# optoisolator-shield.net
KiCad netlist of a schematic drawn in EAGLE
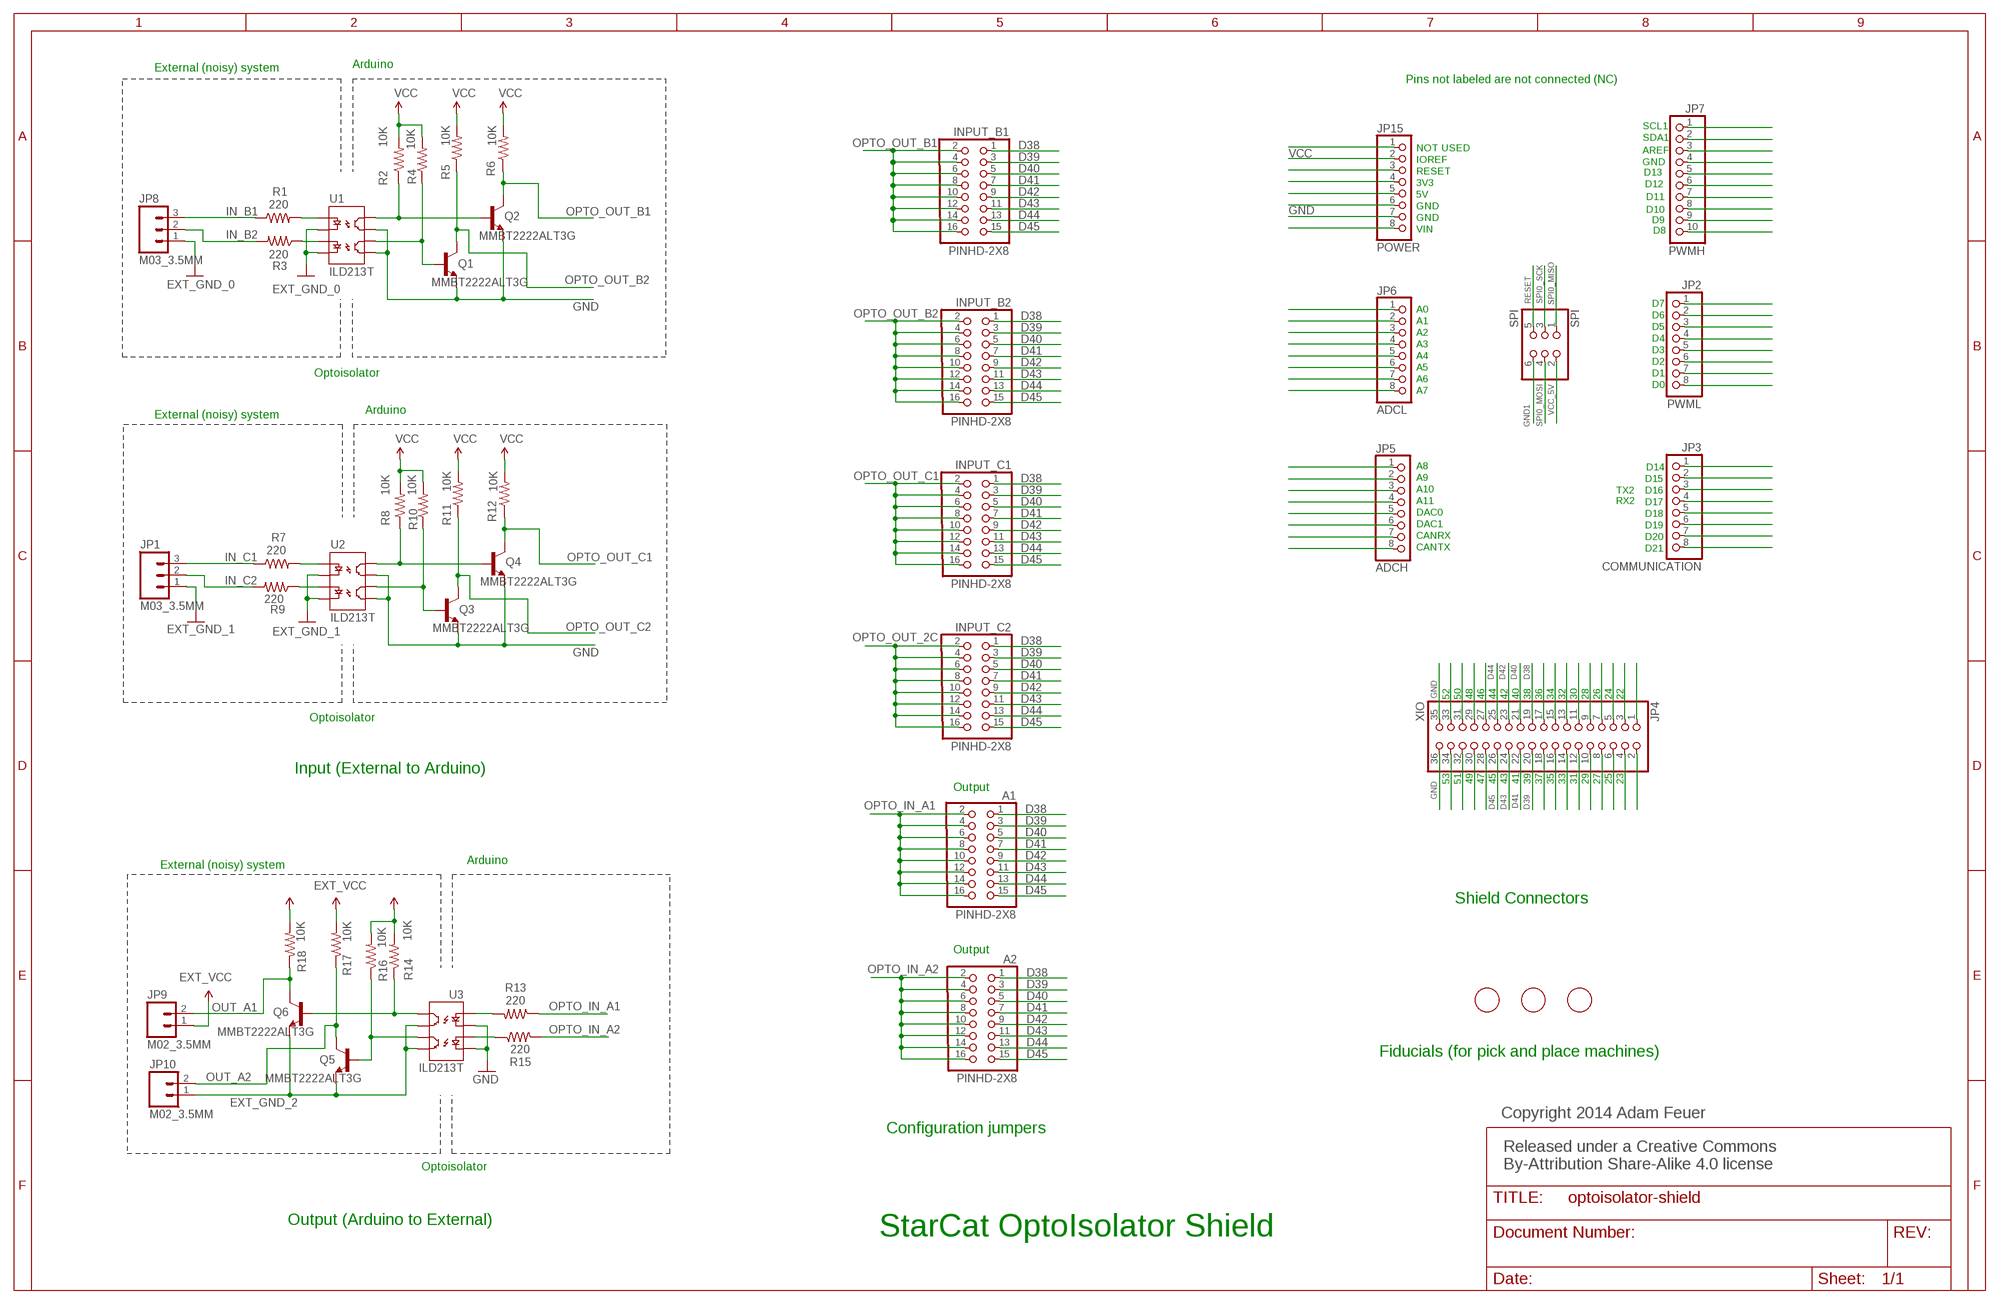
[diagram p0: schematic, sheet 1]

(export (version "E")
  (design (tool "Eeschema 10.0.6"))
  (components
    (comp (ref "A1")
      (value "PINHD-2X8")
      (footprint "eagle-import:2X08")
      (libsource (lib "eagle-import") (part "PINHD-2X8"))
    )
    (comp (ref "A2")
      (value "PINHD-2X8")
      (footprint "eagle-import:2X08")
      (libsource (lib "eagle-import") (part "PINHD-2X8"))
    )
    (comp (ref "INPUT_B1")
      (value "PINHD-2X8")
      (footprint "eagle-import:2X08")
      (libsource (lib "eagle-import") (part "PINHD-2X8"))
    )
    (comp (ref "INPUT_B2")
      (value "PINHD-2X8")
      (footprint "eagle-import:2X08")
      (libsource (lib "eagle-import") (part "PINHD-2X8"))
    )
    (comp (ref "INPUT_C1")
      (value "PINHD-2X8")
      (footprint "eagle-import:2X08")
      (libsource (lib "eagle-import") (part "PINHD-2X8"))
    )
    (comp (ref "INPUT_C2")
      (value "PINHD-2X8")
      (footprint "eagle-import:2X08")
      (libsource (lib "eagle-import") (part "PINHD-2X8"))
    )
    (comp (ref "JP1")
      (value "M03_3.5MM")
      (footprint "eagle-import:SCREWTERMINAL-3.5MM-3")
      (libsource (lib "eagle-import") (part "M03SCREW"))
    )
    (comp (ref "JP2")
      (value "PWML")
      (footprint "eagle-import:1X08")
      (libsource (lib "eagle-import") (part "PINHD-1X8"))
    )
    (comp (ref "JP3")
      (value "COMMUNICATION")
      (footprint "eagle-import:1X08")
      (libsource (lib "eagle-import") (part "PINHD-1X8"))
    )
    (comp (ref "JP4")
      (value "XIO")
      (footprint "eagle-import:2X18")
      (libsource (lib "eagle-import") (part "PINHD-2X18"))
    )
    (comp (ref "JP5")
      (value "ADCH")
      (footprint "eagle-import:1X08")
      (libsource (lib "eagle-import") (part "PINHD-1X8"))
    )
    (comp (ref "JP6")
      (value "ADCL")
      (footprint "eagle-import:1X08")
      (libsource (lib "eagle-import") (part "PINHD-1X8"))
    )
    (comp (ref "JP7")
      (value "PWMH")
      (footprint "eagle-import:1X10")
      (libsource (lib "eagle-import") (part "PINHD-1X10"))
    )
    (comp (ref "JP8")
      (value "M03_3.5MM")
      (footprint "eagle-import:SCREWTERMINAL-3.5MM-3")
      (libsource (lib "eagle-import") (part "M03SCREW"))
    )
    (comp (ref "JP9")
      (value "M02_3.5MM")
      (footprint "eagle-import:SCREWTERMINAL-3.5MM-2")
      (libsource (lib "eagle-import") (part "M023.5MM"))
    )
    (comp (ref "JP10")
      (value "M02_3.5MM")
      (footprint "eagle-import:SCREWTERMINAL-3.5MM-2")
      (libsource (lib "eagle-import") (part "M023.5MM"))
    )
    (comp (ref "JP15")
      (value "POWER")
      (footprint "eagle-import:1X08")
      (libsource (lib "eagle-import") (part "PINHD-1X8"))
    )
    (comp (ref "Q1")
      (value "MMBT2222ALT3G")
      (footprint "eagle-import:SOT23-3")
      (libsource (lib "eagle-import") (part "TRANSISTOR_NPNSOT23-3"))
    )
    (comp (ref "Q2")
      (value "MMBT2222ALT3G")
      (footprint "eagle-import:SOT23-3")
      (libsource (lib "eagle-import") (part "TRANSISTOR_NPNSOT23-3"))
    )
    (comp (ref "Q3")
      (value "MMBT2222ALT3G")
      (footprint "eagle-import:SOT23-3")
      (libsource (lib "eagle-import") (part "TRANSISTOR_NPNSOT23-3"))
    )
    (comp (ref "Q4")
      (value "MMBT2222ALT3G")
      (footprint "eagle-import:SOT23-3")
      (libsource (lib "eagle-import") (part "TRANSISTOR_NPNSOT23-3"))
    )
    (comp (ref "Q5")
      (value "MMBT2222ALT3G")
      (footprint "eagle-import:SOT23-3")
      (libsource (lib "eagle-import") (part "TRANSISTOR_NPNSOT23-3"))
    )
    (comp (ref "Q6")
      (value "MMBT2222ALT3G")
      (footprint "eagle-import:SOT23-3")
      (libsource (lib "eagle-import") (part "TRANSISTOR_NPNSOT23-3"))
    )
    (comp (ref "R1")
      (value "220")
      (footprint "eagle-import:0603-RES")
      (libsource (lib "eagle-import") (part "RESISTOR0603-RES"))
    )
    (comp (ref "R2")
      (value "10K")
      (footprint "eagle-import:0603-RES")
      (libsource (lib "eagle-import") (part "RESISTOR0603-RES"))
    )
    (comp (ref "R3")
      (value "220")
      (footprint "eagle-import:0603-RES")
      (libsource (lib "eagle-import") (part "RESISTOR0603-RES"))
    )
    (comp (ref "R4")
      (value "10K")
      (footprint "eagle-import:0603-RES")
      (libsource (lib "eagle-import") (part "RESISTOR0603-RES"))
    )
    (comp (ref "R5")
      (value "10K")
      (footprint "eagle-import:0603-RES")
      (libsource (lib "eagle-import") (part "RESISTOR0603-RES"))
    )
    (comp (ref "R6")
      (value "10K")
      (footprint "eagle-import:0603-RES")
      (libsource (lib "eagle-import") (part "RESISTOR0603-RES"))
    )
    (comp (ref "R7")
      (value "220")
      (footprint "eagle-import:0603-RES")
      (libsource (lib "eagle-import") (part "RESISTOR0603-RES"))
    )
    (comp (ref "R8")
      (value "10K")
      (footprint "eagle-import:0603-RES")
      (libsource (lib "eagle-import") (part "RESISTOR0603-RES"))
    )
    (comp (ref "R9")
      (value "220")
      (footprint "eagle-import:0603-RES")
      (libsource (lib "eagle-import") (part "RESISTOR0603-RES"))
    )
    (comp (ref "R10")
      (value "10K")
      (footprint "eagle-import:0603-RES")
      (libsource (lib "eagle-import") (part "RESISTOR0603-RES"))
    )
    (comp (ref "R11")
      (value "10K")
      (footprint "eagle-import:0603-RES")
      (libsource (lib "eagle-import") (part "RESISTOR0603-RES"))
    )
    (comp (ref "R12")
      (value "10K")
      (footprint "eagle-import:0603-RES")
      (libsource (lib "eagle-import") (part "RESISTOR0603-RES"))
    )
    (comp (ref "R13")
      (value "220")
      (footprint "eagle-import:0603-RES")
      (libsource (lib "eagle-import") (part "RESISTOR0603-RES"))
    )
    (comp (ref "R14")
      (value "10K")
      (footprint "eagle-import:0603-RES")
      (libsource (lib "eagle-import") (part "RESISTOR0603-RES"))
    )
    (comp (ref "R15")
      (value "220")
      (footprint "eagle-import:0603-RES")
      (libsource (lib "eagle-import") (part "RESISTOR0603-RES"))
    )
    (comp (ref "R16")
      (value "10K")
      (footprint "eagle-import:0603-RES")
      (libsource (lib "eagle-import") (part "RESISTOR0603-RES"))
    )
    (comp (ref "R17")
      (value "10K")
      (footprint "eagle-import:0603-RES")
      (libsource (lib "eagle-import") (part "RESISTOR0603-RES"))
    )
    (comp (ref "R18")
      (value "10K")
      (footprint "eagle-import:0603-RES")
      (libsource (lib "eagle-import") (part "RESISTOR0603-RES"))
    )
    (comp (ref "SPI")
      (value "SPI")
      (footprint "eagle-import:2X03")
      (libsource (lib "eagle-import") (part "PINHD-2X3"))
    )
    (comp (ref "U$2")
      (value "FIDUCIAL")
      (footprint "eagle-import:FIDUCIAL_1MM")
      (libsource (lib "eagle-import") (part "FIDUCIAL"))
    )
    (comp (ref "U$5")
      (value "FIDUCIAL")
      (footprint "eagle-import:FIDUCIAL_1MM")
      (libsource (lib "eagle-import") (part "FIDUCIAL"))
    )
    (comp (ref "U$6")
      (value "FIDUCIAL")
      (footprint "eagle-import:FIDUCIAL_1MM")
      (libsource (lib "eagle-import") (part "FIDUCIAL"))
    )
    (comp (ref "U1")
      (value "ILD213T")
      (footprint "eagle-import:SO08-2")
      (libsource (lib "eagle-import") (part "OPTOISOLATOR-2SOIC8"))
    )
    (comp (ref "U2")
      (value "ILD213T")
      (footprint "eagle-import:SO08-2")
      (libsource (lib "eagle-import") (part "OPTOISOLATOR-2SOIC8"))
    )
    (comp (ref "U3")
      (value "ILD213T")
      (footprint "eagle-import:SO08-2")
      (libsource (lib "eagle-import") (part "OPTOISOLATOR-2SOIC8"))
    )
  )
  (nets
    (net (code "1") (name "/D38") (class "Default")
      (node (ref "A1") (pin "1") (pinfunction "1_1") (pintype "passive"))
      (node (ref "A2") (pin "1") (pinfunction "1_1") (pintype "passive"))
      (node (ref "INPUT_B1") (pin "1") (pinfunction "1_1") (pintype "passive"))
      (node (ref "INPUT_B2") (pin "1") (pinfunction "1_1") (pintype "passive"))
      (node (ref "INPUT_C1") (pin "1") (pinfunction "1_1") (pintype "passive"))
      (node (ref "INPUT_C2") (pin "1") (pinfunction "1_1") (pintype "passive"))
      (node (ref "JP4") (pin "19") (pinfunction "19_19") (pintype "passive"))
    )
    (net (code "2") (name "/D39") (class "Default")
      (node (ref "A1") (pin "3") (pinfunction "3_3") (pintype "passive"))
      (node (ref "A2") (pin "3") (pinfunction "3_3") (pintype "passive"))
      (node (ref "INPUT_B1") (pin "3") (pinfunction "3_3") (pintype "passive"))
      (node (ref "INPUT_B2") (pin "3") (pinfunction "3_3") (pintype "passive"))
      (node (ref "INPUT_C1") (pin "3") (pinfunction "3_3") (pintype "passive"))
      (node (ref "INPUT_C2") (pin "3") (pinfunction "3_3") (pintype "passive"))
      (node (ref "JP4") (pin "20") (pinfunction "20_20") (pintype "passive"))
    )
    (net (code "3") (name "/D40") (class "Default")
      (node (ref "A1") (pin "5") (pinfunction "5_5") (pintype "passive"))
      (node (ref "A2") (pin "5") (pinfunction "5_5") (pintype "passive"))
      (node (ref "INPUT_B1") (pin "5") (pinfunction "5_5") (pintype "passive"))
      (node (ref "INPUT_B2") (pin "5") (pinfunction "5_5") (pintype "passive"))
      (node (ref "INPUT_C1") (pin "5") (pinfunction "5_5") (pintype "passive"))
      (node (ref "INPUT_C2") (pin "5") (pinfunction "5_5") (pintype "passive"))
      (node (ref "JP4") (pin "21") (pinfunction "21_21") (pintype "passive"))
    )
    (net (code "4") (name "/D41") (class "Default")
      (node (ref "A1") (pin "7") (pinfunction "7_7") (pintype "passive"))
      (node (ref "A2") (pin "7") (pinfunction "7_7") (pintype "passive"))
      (node (ref "INPUT_B1") (pin "7") (pinfunction "7_7") (pintype "passive"))
      (node (ref "INPUT_B2") (pin "7") (pinfunction "7_7") (pintype "passive"))
      (node (ref "INPUT_C1") (pin "7") (pinfunction "7_7") (pintype "passive"))
      (node (ref "INPUT_C2") (pin "7") (pinfunction "7_7") (pintype "passive"))
      (node (ref "JP4") (pin "22") (pinfunction "22_22") (pintype "passive"))
    )
    (net (code "5") (name "/D42") (class "Default")
      (node (ref "A1") (pin "9") (pinfunction "9_9") (pintype "passive"))
      (node (ref "A2") (pin "9") (pinfunction "9_9") (pintype "passive"))
      (node (ref "INPUT_B1") (pin "9") (pinfunction "9_9") (pintype "passive"))
      (node (ref "INPUT_B2") (pin "9") (pinfunction "9_9") (pintype "passive"))
      (node (ref "INPUT_C1") (pin "9") (pinfunction "9_9") (pintype "passive"))
      (node (ref "INPUT_C2") (pin "9") (pinfunction "9_9") (pintype "passive"))
      (node (ref "JP4") (pin "23") (pinfunction "23_23") (pintype "passive"))
    )
    (net (code "6") (name "/D43") (class "Default")
      (node (ref "A1") (pin "11") (pinfunction "11_11") (pintype "passive"))
      (node (ref "A2") (pin "11") (pinfunction "11_11") (pintype "passive"))
      (node (ref "INPUT_B1") (pin "11") (pinfunction "11_11") (pintype "passive"))
      (node (ref "INPUT_B2") (pin "11") (pinfunction "11_11") (pintype "passive"))
      (node (ref "INPUT_C1") (pin "11") (pinfunction "11_11") (pintype "passive"))
      (node (ref "INPUT_C2") (pin "11") (pinfunction "11_11") (pintype "passive"))
      (node (ref "JP4") (pin "24") (pinfunction "24_24") (pintype "passive"))
    )
    (net (code "7") (name "/D44") (class "Default")
      (node (ref "A1") (pin "13") (pinfunction "13_13") (pintype "passive"))
      (node (ref "A2") (pin "13") (pinfunction "13_13") (pintype "passive"))
      (node (ref "INPUT_B1") (pin "13") (pinfunction "13_13") (pintype "passive"))
      (node (ref "INPUT_B2") (pin "13") (pinfunction "13_13") (pintype "passive"))
      (node (ref "INPUT_C1") (pin "13") (pinfunction "13_13") (pintype "passive"))
      (node (ref "INPUT_C2") (pin "13") (pinfunction "13_13") (pintype "passive"))
      (node (ref "JP4") (pin "25") (pinfunction "25_25") (pintype "passive"))
    )
    (net (code "8") (name "/D45") (class "Default")
      (node (ref "A1") (pin "15") (pinfunction "15_15") (pintype "passive"))
      (node (ref "A2") (pin "15") (pinfunction "15_15") (pintype "passive"))
      (node (ref "INPUT_B1") (pin "15") (pinfunction "15_15") (pintype "passive"))
      (node (ref "INPUT_B2") (pin "15") (pinfunction "15_15") (pintype "passive"))
      (node (ref "INPUT_C1") (pin "15") (pinfunction "15_15") (pintype "passive"))
      (node (ref "INPUT_C2") (pin "15") (pinfunction "15_15") (pintype "passive"))
      (node (ref "JP4") (pin "26") (pinfunction "26_26") (pintype "passive"))
    )
    (net (code "9") (name "/EXT_GND_2") (class "Default")
      (node (ref "JP10") (pin "1") (pinfunction "1_1") (pintype "passive"))
      (node (ref "Q5") (pin "2") (pinfunction "E_2") (pintype "passive"))
      (node (ref "Q6") (pin "2") (pinfunction "E_2") (pintype "passive"))
      (node (ref "U3") (pin "5") (pinfunction "EM2_5") (pintype "bidirectional"))
      (node (ref "U3") (pin "7") (pinfunction "EM1_7") (pintype "bidirectional"))
    )
    (net (code "10") (name "/GND1") (class "Default")
      (node (ref "SPI") (pin "6") (pinfunction "6_6") (pintype "passive"))
    )
    (net (code "11") (name "/IN_B1") (class "Default")
      (node (ref "JP8") (pin "3") (pinfunction "3_3") (pintype "passive"))
      (node (ref "R1") (pin "1") (pinfunction "1_1") (pintype "passive"))
    )
    (net (code "12") (name "/IN_B2") (class "Default")
      (node (ref "JP8") (pin "2") (pinfunction "2_2") (pintype "passive"))
      (node (ref "R3") (pin "2") (pinfunction "2_2") (pintype "passive"))
    )
    (net (code "13") (name "/IN_C1") (class "Default")
      (node (ref "JP1") (pin "3") (pinfunction "3_3") (pintype "passive"))
      (node (ref "R7") (pin "1") (pinfunction "1_1") (pintype "passive"))
    )
    (net (code "14") (name "/IN_C2") (class "Default")
      (node (ref "JP1") (pin "2") (pinfunction "2_2") (pintype "passive"))
      (node (ref "R9") (pin "2") (pinfunction "2_2") (pintype "passive"))
    )
    (net (code "15") (name "/OPTO_IN_A1") (class "Default")
      (node (ref "A1") (pin "10") (pinfunction "10_10") (pintype "passive"))
      (node (ref "A1") (pin "12") (pinfunction "12_12") (pintype "passive"))
      (node (ref "A1") (pin "14") (pinfunction "14_14") (pintype "passive"))
      (node (ref "A1") (pin "16") (pinfunction "16_16") (pintype "passive"))
      (node (ref "A1") (pin "2") (pinfunction "2_2") (pintype "passive"))
      (node (ref "A1") (pin "4") (pinfunction "4_4") (pintype "passive"))
      (node (ref "A1") (pin "6") (pinfunction "6_6") (pintype "passive"))
      (node (ref "A1") (pin "8") (pinfunction "8_8") (pintype "passive"))
      (node (ref "R13") (pin "1") (pinfunction "1_1") (pintype "passive"))
    )
    (net (code "16") (name "/OPTO_IN_A2") (class "Default")
      (node (ref "A2") (pin "10") (pinfunction "10_10") (pintype "passive"))
      (node (ref "A2") (pin "12") (pinfunction "12_12") (pintype "passive"))
      (node (ref "A2") (pin "14") (pinfunction "14_14") (pintype "passive"))
      (node (ref "A2") (pin "16") (pinfunction "16_16") (pintype "passive"))
      (node (ref "A2") (pin "2") (pinfunction "2_2") (pintype "passive"))
      (node (ref "A2") (pin "4") (pinfunction "4_4") (pintype "passive"))
      (node (ref "A2") (pin "6") (pinfunction "6_6") (pintype "passive"))
      (node (ref "A2") (pin "8") (pinfunction "8_8") (pintype "passive"))
      (node (ref "R15") (pin "2") (pinfunction "2_2") (pintype "passive"))
    )
    (net (code "17") (name "/OPTO_OUT_2C") (class "Default")
      (node (ref "INPUT_C2") (pin "10") (pinfunction "10_10") (pintype "passive"))
      (node (ref "INPUT_C2") (pin "12") (pinfunction "12_12") (pintype "passive"))
      (node (ref "INPUT_C2") (pin "14") (pinfunction "14_14") (pintype "passive"))
      (node (ref "INPUT_C2") (pin "16") (pinfunction "16_16") (pintype "passive"))
      (node (ref "INPUT_C2") (pin "2") (pinfunction "2_2") (pintype "passive"))
      (node (ref "INPUT_C2") (pin "4") (pinfunction "4_4") (pintype "passive"))
      (node (ref "INPUT_C2") (pin "6") (pinfunction "6_6") (pintype "passive"))
      (node (ref "INPUT_C2") (pin "8") (pinfunction "8_8") (pintype "passive"))
    )
    (net (code "18") (name "/OPTO_OUT_B1") (class "Default")
      (node (ref "INPUT_B1") (pin "10") (pinfunction "10_10") (pintype "passive"))
      (node (ref "INPUT_B1") (pin "12") (pinfunction "12_12") (pintype "passive"))
      (node (ref "INPUT_B1") (pin "14") (pinfunction "14_14") (pintype "passive"))
      (node (ref "INPUT_B1") (pin "16") (pinfunction "16_16") (pintype "passive"))
      (node (ref "INPUT_B1") (pin "2") (pinfunction "2_2") (pintype "passive"))
      (node (ref "INPUT_B1") (pin "4") (pinfunction "4_4") (pintype "passive"))
      (node (ref "INPUT_B1") (pin "6") (pinfunction "6_6") (pintype "passive"))
      (node (ref "INPUT_B1") (pin "8") (pinfunction "8_8") (pintype "passive"))
      (node (ref "Q2") (pin "3") (pinfunction "C_3") (pintype "passive"))
      (node (ref "R6") (pin "1") (pinfunction "1_1") (pintype "passive"))
    )
    (net (code "19") (name "/OPTO_OUT_B2") (class "Default")
      (node (ref "INPUT_B2") (pin "10") (pinfunction "10_10") (pintype "passive"))
      (node (ref "INPUT_B2") (pin "12") (pinfunction "12_12") (pintype "passive"))
      (node (ref "INPUT_B2") (pin "14") (pinfunction "14_14") (pintype "passive"))
      (node (ref "INPUT_B2") (pin "16") (pinfunction "16_16") (pintype "passive"))
      (node (ref "INPUT_B2") (pin "2") (pinfunction "2_2") (pintype "passive"))
      (node (ref "INPUT_B2") (pin "4") (pinfunction "4_4") (pintype "passive"))
      (node (ref "INPUT_B2") (pin "6") (pinfunction "6_6") (pintype "passive"))
      (node (ref "INPUT_B2") (pin "8") (pinfunction "8_8") (pintype "passive"))
      (node (ref "Q1") (pin "3") (pinfunction "C_3") (pintype "passive"))
      (node (ref "R5") (pin "1") (pinfunction "1_1") (pintype "passive"))
    )
    (net (code "20") (name "/OPTO_OUT_C1") (class "Default")
      (node (ref "INPUT_C1") (pin "10") (pinfunction "10_10") (pintype "passive"))
      (node (ref "INPUT_C1") (pin "12") (pinfunction "12_12") (pintype "passive"))
      (node (ref "INPUT_C1") (pin "14") (pinfunction "14_14") (pintype "passive"))
      (node (ref "INPUT_C1") (pin "16") (pinfunction "16_16") (pintype "passive"))
      (node (ref "INPUT_C1") (pin "2") (pinfunction "2_2") (pintype "passive"))
      (node (ref "INPUT_C1") (pin "4") (pinfunction "4_4") (pintype "passive"))
      (node (ref "INPUT_C1") (pin "6") (pinfunction "6_6") (pintype "passive"))
      (node (ref "INPUT_C1") (pin "8") (pinfunction "8_8") (pintype "passive"))
      (node (ref "Q4") (pin "3") (pinfunction "C_3") (pintype "passive"))
      (node (ref "R12") (pin "1") (pinfunction "1_1") (pintype "passive"))
    )
    (net (code "21") (name "/OPTO_OUT_C2") (class "Default")
      (node (ref "Q3") (pin "3") (pinfunction "C_3") (pintype "passive"))
      (node (ref "R11") (pin "1") (pinfunction "1_1") (pintype "passive"))
    )
    (net (code "22") (name "/OUT_A1") (class "Default")
      (node (ref "JP9") (pin "2") (pinfunction "2_2") (pintype "passive"))
      (node (ref "Q6") (pin "3") (pinfunction "C_3") (pintype "passive"))
      (node (ref "R18") (pin "1") (pinfunction "1_1") (pintype "passive"))
    )
    (net (code "23") (name "/OUT_A2") (class "Default")
      (node (ref "JP10") (pin "2") (pinfunction "2_2") (pintype "passive"))
      (node (ref "Q5") (pin "3") (pinfunction "C_3") (pintype "passive"))
      (node (ref "R17") (pin "1") (pinfunction "1_1") (pintype "passive"))
    )
    (net (code "24") (name "/RESET") (class "Default")
      (node (ref "SPI") (pin "5") (pinfunction "5_5") (pintype "passive"))
    )
    (net (code "25") (name "/SPI0_MISO") (class "Default")
      (node (ref "SPI") (pin "1") (pinfunction "1_1") (pintype "passive"))
    )
    (net (code "26") (name "/SPI0_MOSI") (class "Default")
      (node (ref "SPI") (pin "4") (pinfunction "4_4") (pintype "passive"))
    )
    (net (code "27") (name "/SPI0_SCK") (class "Default")
      (node (ref "SPI") (pin "3") (pinfunction "3_3") (pintype "passive"))
    )
    (net (code "28") (name "/VCC_5V") (class "Default")
      (node (ref "SPI") (pin "2") (pinfunction "2_2") (pintype "passive"))
    )
    (net (code "29") (name "EXTERNAL_VCC") (class "Default")
      (node (ref "JP9") (pin "1") (pinfunction "1_1") (pintype "passive"))
      (node (ref "R14") (pin "2") (pinfunction "2_2") (pintype "passive"))
      (node (ref "R16") (pin "2") (pinfunction "2_2") (pintype "passive"))
      (node (ref "R17") (pin "2") (pinfunction "2_2") (pintype "passive"))
      (node (ref "R18") (pin "2") (pinfunction "2_2") (pintype "passive"))
    )
    (net (code "30") (name "EXT_GND_0") (class "Default")
      (node (ref "JP8") (pin "1") (pinfunction "1_1") (pintype "passive"))
      (node (ref "U1") (pin "2") (pinfunction "C1_2") (pintype "bidirectional"))
      (node (ref "U1") (pin "4") (pinfunction "C2_4") (pintype "bidirectional"))
    )
    (net (code "31") (name "EXT_GND_1") (class "Default")
      (node (ref "JP1") (pin "1") (pinfunction "1_1") (pintype "passive"))
      (node (ref "U2") (pin "2") (pinfunction "C1_2") (pintype "bidirectional"))
      (node (ref "U2") (pin "4") (pinfunction "C2_4") (pintype "bidirectional"))
    )
    (net (code "32") (name "GND") (class "Default")
      (node (ref "JP15") (pin "7") (pinfunction "7_7") (pintype "passive"))
      (node (ref "JP4") (pin "35") (pinfunction "35_35") (pintype "passive"))
      (node (ref "JP4") (pin "36") (pinfunction "36_36") (pintype "passive"))
      (node (ref "Q1") (pin "2") (pinfunction "E_2") (pintype "passive"))
      (node (ref "Q2") (pin "2") (pinfunction "E_2") (pintype "passive"))
      (node (ref "Q3") (pin "2") (pinfunction "E_2") (pintype "passive"))
      (node (ref "Q4") (pin "2") (pinfunction "E_2") (pintype "passive"))
      (node (ref "U1") (pin "5") (pinfunction "EM2_5") (pintype "bidirectional"))
      (node (ref "U1") (pin "7") (pinfunction "EM1_7") (pintype "bidirectional"))
      (node (ref "U2") (pin "5") (pinfunction "EM2_5") (pintype "bidirectional"))
      (node (ref "U2") (pin "7") (pinfunction "EM1_7") (pintype "bidirectional"))
      (node (ref "U3") (pin "2") (pinfunction "C1_2") (pintype "bidirectional"))
      (node (ref "U3") (pin "4") (pinfunction "C2_4") (pintype "bidirectional"))
    )
    (net (code "33") (name "Net-(Q1-B)") (class "Default")
      (node (ref "Q1") (pin "1") (pinfunction "B_1") (pintype "passive"))
      (node (ref "R4") (pin "1") (pinfunction "1_1") (pintype "passive"))
      (node (ref "U1") (pin "6") (pinfunction "CL2_6") (pintype "bidirectional"))
    )
    (net (code "34") (name "Net-(Q2-B)") (class "Default")
      (node (ref "Q2") (pin "1") (pinfunction "B_1") (pintype "passive"))
      (node (ref "R2") (pin "1") (pinfunction "1_1") (pintype "passive"))
      (node (ref "U1") (pin "8") (pinfunction "CL1_8") (pintype "bidirectional"))
    )
    (net (code "35") (name "Net-(Q3-B)") (class "Default")
      (node (ref "Q3") (pin "1") (pinfunction "B_1") (pintype "passive"))
      (node (ref "R10") (pin "1") (pinfunction "1_1") (pintype "passive"))
      (node (ref "U2") (pin "6") (pinfunction "CL2_6") (pintype "bidirectional"))
    )
    (net (code "36") (name "Net-(Q4-B)") (class "Default")
      (node (ref "Q4") (pin "1") (pinfunction "B_1") (pintype "passive"))
      (node (ref "R8") (pin "1") (pinfunction "1_1") (pintype "passive"))
      (node (ref "U2") (pin "8") (pinfunction "CL1_8") (pintype "bidirectional"))
    )
    (net (code "37") (name "Net-(Q5-B)") (class "Default")
      (node (ref "Q5") (pin "1") (pinfunction "B_1") (pintype "passive"))
      (node (ref "R16") (pin "1") (pinfunction "1_1") (pintype "passive"))
      (node (ref "U3") (pin "6") (pinfunction "CL2_6") (pintype "bidirectional"))
    )
    (net (code "38") (name "Net-(Q6-B)") (class "Default")
      (node (ref "Q6") (pin "1") (pinfunction "B_1") (pintype "passive"))
      (node (ref "R14") (pin "1") (pinfunction "1_1") (pintype "passive"))
      (node (ref "U3") (pin "8") (pinfunction "CL1_8") (pintype "bidirectional"))
    )
    (net (code "39") (name "Net-(U1-A1)") (class "Default")
      (node (ref "R1") (pin "2") (pinfunction "2_2") (pintype "passive"))
      (node (ref "U1") (pin "1") (pinfunction "A1_1") (pintype "bidirectional"))
    )
    (net (code "40") (name "Net-(U1-A2)") (class "Default")
      (node (ref "R3") (pin "1") (pinfunction "1_1") (pintype "passive"))
      (node (ref "U1") (pin "3") (pinfunction "A2_3") (pintype "bidirectional"))
    )
    (net (code "41") (name "Net-(U2-A1)") (class "Default")
      (node (ref "R7") (pin "2") (pinfunction "2_2") (pintype "passive"))
      (node (ref "U2") (pin "1") (pinfunction "A1_1") (pintype "bidirectional"))
    )
    (net (code "42") (name "Net-(U2-A2)") (class "Default")
      (node (ref "R9") (pin "1") (pinfunction "1_1") (pintype "passive"))
      (node (ref "U2") (pin "3") (pinfunction "A2_3") (pintype "bidirectional"))
    )
    (net (code "43") (name "Net-(U3-A1)") (class "Default")
      (node (ref "R13") (pin "2") (pinfunction "2_2") (pintype "passive"))
      (node (ref "U3") (pin "1") (pinfunction "A1_1") (pintype "bidirectional"))
    )
    (net (code "44") (name "Net-(U3-A2)") (class "Default")
      (node (ref "R15") (pin "1") (pinfunction "1_1") (pintype "passive"))
      (node (ref "U3") (pin "3") (pinfunction "A2_3") (pintype "bidirectional"))
    )
    (net (code "45") (name "VCC") (class "Default")
      (node (ref "JP15") (pin "2") (pinfunction "2_2") (pintype "passive"))
      (node (ref "R10") (pin "2") (pinfunction "2_2") (pintype "passive"))
      (node (ref "R11") (pin "2") (pinfunction "2_2") (pintype "passive"))
      (node (ref "R12") (pin "2") (pinfunction "2_2") (pintype "passive"))
      (node (ref "R2") (pin "2") (pinfunction "2_2") (pintype "passive"))
      (node (ref "R4") (pin "2") (pinfunction "2_2") (pintype "passive"))
      (node (ref "R5") (pin "2") (pinfunction "2_2") (pintype "passive"))
      (node (ref "R6") (pin "2") (pinfunction "2_2") (pintype "passive"))
      (node (ref "R8") (pin "2") (pinfunction "2_2") (pintype "passive"))
    )
    (net (code "46") (name "unconnected-(JP2-Pad1)") (class "Default")
      (node (ref "JP2") (pin "1") (pinfunction "1_1") (pintype "passive"))
    )
    (net (code "47") (name "unconnected-(JP2-Pad2)") (class "Default")
      (node (ref "JP2") (pin "2") (pinfunction "2_2") (pintype "passive"))
    )
    (net (code "48") (name "unconnected-(JP2-Pad3)") (class "Default")
      (node (ref "JP2") (pin "3") (pinfunction "3_3") (pintype "passive"))
    )
    (net (code "49") (name "unconnected-(JP2-Pad4)") (class "Default")
      (node (ref "JP2") (pin "4") (pinfunction "4_4") (pintype "passive"))
    )
    (net (code "50") (name "unconnected-(JP2-Pad5)") (class "Default")
      (node (ref "JP2") (pin "5") (pinfunction "5_5") (pintype "passive"))
    )
    (net (code "51") (name "unconnected-(JP2-Pad6)") (class "Default")
      (node (ref "JP2") (pin "6") (pinfunction "6_6") (pintype "passive"))
    )
    (net (code "52") (name "unconnected-(JP2-Pad7)") (class "Default")
      (node (ref "JP2") (pin "7") (pinfunction "7_7") (pintype "passive"))
    )
    (net (code "53") (name "unconnected-(JP2-Pad8)") (class "Default")
      (node (ref "JP2") (pin "8") (pinfunction "8_8") (pintype "passive"))
    )
    (net (code "54") (name "unconnected-(JP3-Pad1)") (class "Default")
      (node (ref "JP3") (pin "1") (pinfunction "1_1") (pintype "passive"))
    )
    (net (code "55") (name "unconnected-(JP3-Pad2)") (class "Default")
      (node (ref "JP3") (pin "2") (pinfunction "2_2") (pintype "passive"))
    )
    (net (code "56") (name "unconnected-(JP3-Pad3)") (class "Default")
      (node (ref "JP3") (pin "3") (pinfunction "3_3") (pintype "passive"))
    )
    (net (code "57") (name "unconnected-(JP3-Pad4)") (class "Default")
      (node (ref "JP3") (pin "4") (pinfunction "4_4") (pintype "passive"))
    )
    (net (code "58") (name "unconnected-(JP3-Pad5)") (class "Default")
      (node (ref "JP3") (pin "5") (pinfunction "5_5") (pintype "passive"))
    )
    (net (code "59") (name "unconnected-(JP3-Pad6)") (class "Default")
      (node (ref "JP3") (pin "6") (pinfunction "6_6") (pintype "passive"))
    )
    (net (code "60") (name "unconnected-(JP3-Pad7)") (class "Default")
      (node (ref "JP3") (pin "7") (pinfunction "7_7") (pintype "passive"))
    )
    (net (code "61") (name "unconnected-(JP3-Pad8)") (class "Default")
      (node (ref "JP3") (pin "8") (pinfunction "8_8") (pintype "passive"))
    )
    (net (code "62") (name "unconnected-(JP4-Pad1)") (class "Default")
      (node (ref "JP4") (pin "1") (pinfunction "1_1") (pintype "passive"))
    )
    (net (code "63") (name "unconnected-(JP4-Pad2)") (class "Default")
      (node (ref "JP4") (pin "2") (pinfunction "2_2") (pintype "passive"))
    )
    (net (code "64") (name "unconnected-(JP4-Pad3)") (class "Default")
      (node (ref "JP4") (pin "3") (pinfunction "3_3") (pintype "passive"))
    )
    (net (code "65") (name "unconnected-(JP4-Pad4)") (class "Default")
      (node (ref "JP4") (pin "4") (pinfunction "4_4") (pintype "passive"))
    )
    (net (code "66") (name "unconnected-(JP4-Pad5)") (class "Default")
      (node (ref "JP4") (pin "5") (pinfunction "5_5") (pintype "passive"))
    )
    (net (code "67") (name "unconnected-(JP4-Pad6)") (class "Default")
      (node (ref "JP4") (pin "6") (pinfunction "6_6") (pintype "passive"))
    )
    (net (code "68") (name "unconnected-(JP4-Pad7)") (class "Default")
      (node (ref "JP4") (pin "7") (pinfunction "7_7") (pintype "passive"))
    )
    (net (code "69") (name "unconnected-(JP4-Pad8)") (class "Default")
      (node (ref "JP4") (pin "8") (pinfunction "8_8") (pintype "passive"))
    )
    (net (code "70") (name "unconnected-(JP4-Pad9)") (class "Default")
      (node (ref "JP4") (pin "9") (pinfunction "9_9") (pintype "passive"))
    )
    (net (code "71") (name "unconnected-(JP4-Pad10)") (class "Default")
      (node (ref "JP4") (pin "10") (pinfunction "10_10") (pintype "passive"))
    )
    (net (code "72") (name "unconnected-(JP4-Pad11)") (class "Default")
      (node (ref "JP4") (pin "11") (pinfunction "11_11") (pintype "passive"))
    )
    (net (code "73") (name "unconnected-(JP4-Pad12)") (class "Default")
      (node (ref "JP4") (pin "12") (pinfunction "12_12") (pintype "passive"))
    )
    (net (code "74") (name "unconnected-(JP4-Pad13)") (class "Default")
      (node (ref "JP4") (pin "13") (pinfunction "13_13") (pintype "passive"))
    )
    (net (code "75") (name "unconnected-(JP4-Pad14)") (class "Default")
      (node (ref "JP4") (pin "14") (pinfunction "14_14") (pintype "passive"))
    )
    (net (code "76") (name "unconnected-(JP4-Pad15)") (class "Default")
      (node (ref "JP4") (pin "15") (pinfunction "15_15") (pintype "passive"))
    )
    (net (code "77") (name "unconnected-(JP4-Pad16)") (class "Default")
      (node (ref "JP4") (pin "16") (pinfunction "16_16") (pintype "passive"))
    )
    (net (code "78") (name "unconnected-(JP4-Pad17)") (class "Default")
      (node (ref "JP4") (pin "17") (pinfunction "17_17") (pintype "passive"))
    )
    (net (code "79") (name "unconnected-(JP4-Pad18)") (class "Default")
      (node (ref "JP4") (pin "18") (pinfunction "18_18") (pintype "passive"))
    )
    (net (code "80") (name "unconnected-(JP4-Pad27)") (class "Default")
      (node (ref "JP4") (pin "27") (pinfunction "27_27") (pintype "passive"))
    )
    (net (code "81") (name "unconnected-(JP4-Pad28)") (class "Default")
      (node (ref "JP4") (pin "28") (pinfunction "28_28") (pintype "passive"))
    )
    (net (code "82") (name "unconnected-(JP4-Pad29)") (class "Default")
      (node (ref "JP4") (pin "29") (pinfunction "29_29") (pintype "passive"))
    )
    (net (code "83") (name "unconnected-(JP4-Pad30)") (class "Default")
      (node (ref "JP4") (pin "30") (pinfunction "30_30") (pintype "passive"))
    )
    (net (code "84") (name "unconnected-(JP4-Pad31)") (class "Default")
      (node (ref "JP4") (pin "31") (pinfunction "31_31") (pintype "passive"))
    )
    (net (code "85") (name "unconnected-(JP4-Pad32)") (class "Default")
      (node (ref "JP4") (pin "32") (pinfunction "32_32") (pintype "passive"))
    )
    (net (code "86") (name "unconnected-(JP4-Pad33)") (class "Default")
      (node (ref "JP4") (pin "33") (pinfunction "33_33") (pintype "passive"))
    )
    (net (code "87") (name "unconnected-(JP4-Pad34)") (class "Default")
      (node (ref "JP4") (pin "34") (pinfunction "34_34") (pintype "passive"))
    )
    (net (code "88") (name "unconnected-(JP5-Pad1)") (class "Default")
      (node (ref "JP5") (pin "1") (pinfunction "1_1") (pintype "passive"))
    )
    (net (code "89") (name "unconnected-(JP5-Pad2)") (class "Default")
      (node (ref "JP5") (pin "2") (pinfunction "2_2") (pintype "passive"))
    )
    (net (code "90") (name "unconnected-(JP5-Pad3)") (class "Default")
      (node (ref "JP5") (pin "3") (pinfunction "3_3") (pintype "passive"))
    )
    (net (code "91") (name "unconnected-(JP5-Pad4)") (class "Default")
      (node (ref "JP5") (pin "4") (pinfunction "4_4") (pintype "passive"))
    )
    (net (code "92") (name "unconnected-(JP5-Pad5)") (class "Default")
      (node (ref "JP5") (pin "5") (pinfunction "5_5") (pintype "passive"))
    )
    (net (code "93") (name "unconnected-(JP5-Pad6)") (class "Default")
      (node (ref "JP5") (pin "6") (pinfunction "6_6") (pintype "passive"))
    )
    (net (code "94") (name "unconnected-(JP5-Pad7)") (class "Default")
      (node (ref "JP5") (pin "7") (pinfunction "7_7") (pintype "passive"))
    )
    (net (code "95") (name "unconnected-(JP5-Pad8)") (class "Default")
      (node (ref "JP5") (pin "8") (pinfunction "8_8") (pintype "passive"))
    )
    (net (code "96") (name "unconnected-(JP6-Pad1)") (class "Default")
      (node (ref "JP6") (pin "1") (pinfunction "1_1") (pintype "passive"))
    )
    (net (code "97") (name "unconnected-(JP6-Pad2)") (class "Default")
      (node (ref "JP6") (pin "2") (pinfunction "2_2") (pintype "passive"))
    )
    (net (code "98") (name "unconnected-(JP6-Pad3)") (class "Default")
      (node (ref "JP6") (pin "3") (pinfunction "3_3") (pintype "passive"))
    )
    (net (code "99") (name "unconnected-(JP6-Pad4)") (class "Default")
      (node (ref "JP6") (pin "4") (pinfunction "4_4") (pintype "passive"))
    )
    (net (code "100") (name "unconnected-(JP6-Pad5)") (class "Default")
      (node (ref "JP6") (pin "5") (pinfunction "5_5") (pintype "passive"))
    )
    (net (code "101") (name "unconnected-(JP6-Pad6)") (class "Default")
      (node (ref "JP6") (pin "6") (pinfunction "6_6") (pintype "passive"))
    )
    (net (code "102") (name "unconnected-(JP6-Pad7)") (class "Default")
      (node (ref "JP6") (pin "7") (pinfunction "7_7") (pintype "passive"))
    )
    (net (code "103") (name "unconnected-(JP6-Pad8)") (class "Default")
      (node (ref "JP6") (pin "8") (pinfunction "8_8") (pintype "passive"))
    )
    (net (code "104") (name "unconnected-(JP7-Pad1)") (class "Default")
      (node (ref "JP7") (pin "1") (pinfunction "1_1") (pintype "passive"))
    )
    (net (code "105") (name "unconnected-(JP7-Pad2)") (class "Default")
      (node (ref "JP7") (pin "2") (pinfunction "2_2") (pintype "passive"))
    )
    (net (code "106") (name "unconnected-(JP7-Pad3)") (class "Default")
      (node (ref "JP7") (pin "3") (pinfunction "3_3") (pintype "passive"))
    )
    (net (code "107") (name "unconnected-(JP7-Pad4)") (class "Default")
      (node (ref "JP7") (pin "4") (pinfunction "4_4") (pintype "passive"))
    )
    (net (code "108") (name "unconnected-(JP7-Pad5)") (class "Default")
      (node (ref "JP7") (pin "5") (pinfunction "5_5") (pintype "passive"))
    )
    (net (code "109") (name "unconnected-(JP7-Pad6)") (class "Default")
      (node (ref "JP7") (pin "6") (pinfunction "6_6") (pintype "passive"))
    )
    (net (code "110") (name "unconnected-(JP7-Pad7)") (class "Default")
      (node (ref "JP7") (pin "7") (pinfunction "7_7") (pintype "passive"))
    )
    (net (code "111") (name "unconnected-(JP7-Pad8)") (class "Default")
      (node (ref "JP7") (pin "8") (pinfunction "8_8") (pintype "passive"))
    )
    (net (code "112") (name "unconnected-(JP7-Pad9)") (class "Default")
      (node (ref "JP7") (pin "9") (pinfunction "9_9") (pintype "passive"))
    )
    (net (code "113") (name "unconnected-(JP7-Pad10)") (class "Default")
      (node (ref "JP7") (pin "10") (pinfunction "10_10") (pintype "passive"))
    )
    (net (code "114") (name "unconnected-(JP15-Pad1)") (class "Default")
      (node (ref "JP15") (pin "1") (pinfunction "1_1") (pintype "passive"))
    )
    (net (code "115") (name "unconnected-(JP15-Pad3)") (class "Default")
      (node (ref "JP15") (pin "3") (pinfunction "3_3") (pintype "passive"))
    )
    (net (code "116") (name "unconnected-(JP15-Pad4)") (class "Default")
      (node (ref "JP15") (pin "4") (pinfunction "4_4") (pintype "passive"))
    )
    (net (code "117") (name "unconnected-(JP15-Pad5)") (class "Default")
      (node (ref "JP15") (pin "5") (pinfunction "5_5") (pintype "passive"))
    )
    (net (code "118") (name "unconnected-(JP15-Pad6)") (class "Default")
      (node (ref "JP15") (pin "6") (pinfunction "6_6") (pintype "passive"))
    )
    (net (code "119") (name "unconnected-(JP15-Pad8)") (class "Default")
      (node (ref "JP15") (pin "8") (pinfunction "8_8") (pintype "passive"))
    )
  )
)
